# signal_processor_design_of_UAV.net
KiCad netlist of a schematic drawn in Altium Designer
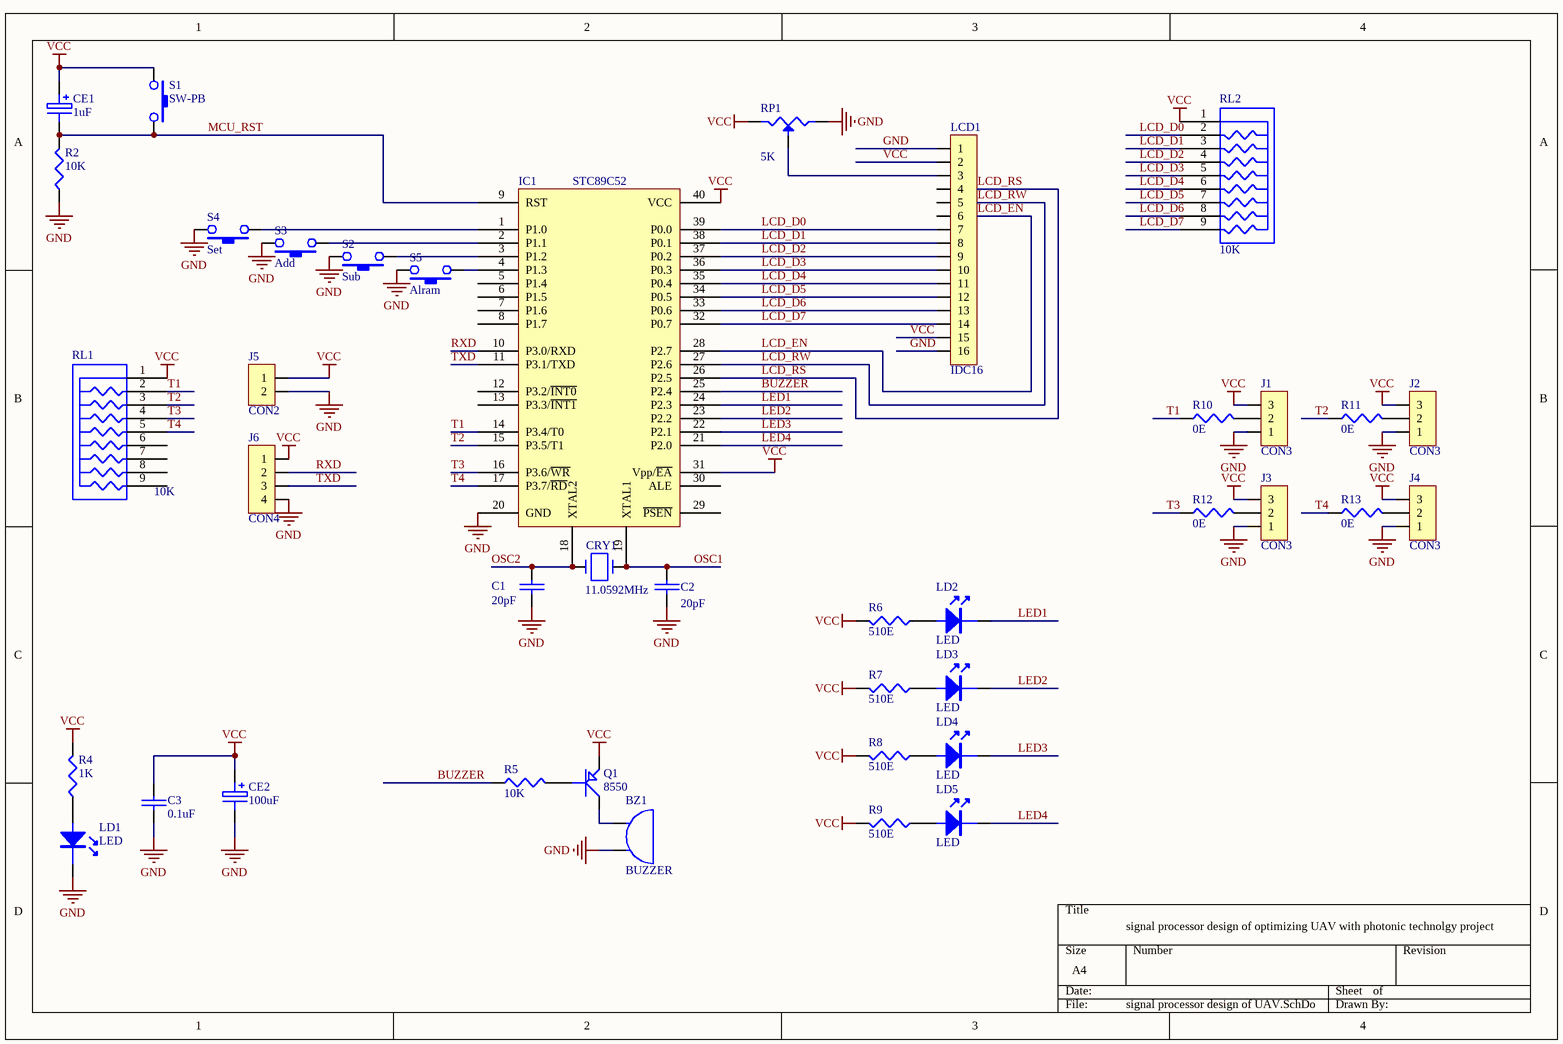
[diagram p0: signal processor design of UAV.SchDoc]

(export (version "E")
  (design (tool "Eeschema 10.0.6"))
  (components
    (comp (ref "BZ1") (value "BUZZER") (footprint "BUZZER1") (libsource (lib "Sch1") (part "BUZZER")))
    (comp (ref "C1")
      (value "20pF")
      (footprint "RAD0.1")
      (description "Capacitor")
      (libsource (lib "*") (part "CAP"))
    )
    (comp (ref "C2")
      (value "20pF")
      (footprint "RAD0.1")
      (description "Capacitor")
      (libsource (lib "*") (part "CAP"))
    )
    (comp (ref "C3") (value "0.1uF") (footprint "RAD0.1") (libsource (lib "Sch1") (part "CAP")))
    (comp (ref "CE1") (value "1uF") (footprint "RB.1/.1L") (libsource (lib "Sch1") (part "ELECTRO1")))
    (comp (ref "CE2") (value "100uF") (footprint "RB.1/.2") (libsource (lib "Sch1") (part "ELECTRO1")))
    (comp (ref "CRY1") (value "11.0592MHz") (footprint "XTAL1") (libsource (lib "*") (part "CRYSTAL")))
    (comp (ref "IC1") (value "STC89C52") (footprint "DIP40") (libsource (lib "Sch") (part "AT89C51")))
    (comp (ref "J1") (value "CON3") (footprint "HJ3P2.54") (libsource (lib "Sch1") (part "CON3")))
    (comp (ref "J2") (value "CON3") (footprint "HJ3P2.54") (libsource (lib "Sch1") (part "CON3")))
    (comp (ref "J3") (value "CON3") (footprint "HJ3P2.54") (libsource (lib "Sch1") (part "CON3")))
    (comp (ref "J4") (value "CON3") (footprint "HJ3P2.54") (libsource (lib "Sch1") (part "CON3")))
    (comp (ref "J5") (value "CON2") (footprint "HJ2P2.54") (libsource (lib "Sch1") (part "CON2")))
    (comp (ref "J6") (value "CON4") (footprint "HJ4P2.54") (libsource (lib "Sch1") (part "CON4")))
    (comp (ref "LCD1") (value "IDC16") (footprint "LCD1602A") (libsource (lib "Sch1") (part "CON16")))
    (comp (ref "LD1") (value "LED") (footprint "LEDF3") (libsource (lib "Sch1") (part "LED")))
    (comp (ref "LD2") (value "LED") (footprint "LEDF3") (libsource (lib "Sch1") (part "LED")))
    (comp (ref "LD3") (value "LED") (footprint "LEDF3") (libsource (lib "Sch1") (part "LED")))
    (comp (ref "LD4") (value "LED") (footprint "LEDF3") (libsource (lib "Sch1") (part "LED")))
    (comp (ref "LD5") (value "LED") (footprint "LEDF3") (libsource (lib "Sch1") (part "LED")))
    (comp (ref "Q1") (value "8550") (footprint "TR-EBC") (libsource (lib "Sch1") (part "PNP1")))
    (comp (ref "R2") (value "10K") (footprint "AXIAL0.3") (libsource (lib "Sch1") (part "RES1")))
    (comp (ref "R4") (value "1K") (footprint "AXIAL0.3") (libsource (lib "Sch1") (part "RES1")))
    (comp (ref "R5") (value "10K") (footprint "AXIAL0.3") (libsource (lib "Sch1") (part "RES1")))
    (comp (ref "R6") (value "510E") (footprint "AXIAL0.3") (libsource (lib "Sch1") (part "RES1")))
    (comp (ref "R7") (value "510E") (footprint "AXIAL0.3") (libsource (lib "Sch1") (part "RES1")))
    (comp (ref "R8") (value "510E") (footprint "AXIAL0.3") (libsource (lib "Sch1") (part "RES1")))
    (comp (ref "R9") (value "510E") (footprint "AXIAL0.3") (libsource (lib "Sch1") (part "RES1")))
    (comp (ref "R10") (value "0E") (footprint "AXIAL0.3") (libsource (lib "Sch1") (part "RES1")))
    (comp (ref "R11") (value "0E") (footprint "AXIAL0.3") (libsource (lib "Sch1") (part "RES1")))
    (comp (ref "R12") (value "0E") (footprint "AXIAL0.3") (libsource (lib "Sch1") (part "RES1")))
    (comp (ref "R13") (value "0E") (footprint "AXIAL0.3") (libsource (lib "Sch1") (part "RES1")))
    (comp (ref "RL1") (value "10K") (footprint "RES9P") (libsource (lib "Sch1") (part "RESL1")))
    (comp (ref "RL2") (value "10K") (footprint "RES9P") (libsource (lib "Sch1") (part "RESL1")))
    (comp (ref "RP1") (value "5K") (footprint "WR1") (libsource (lib "Sch1") (part "POT1")))
    (comp (ref "S1") (value "SW-PB") (footprint "SW-PB4DS") (libsource (lib "Sch1") (part "SW-PB")))
    (comp (ref "S2") (value "Sub") (footprint "SW-PB4DS") (libsource (lib "Sch1") (part "SW-PB")))
    (comp (ref "S3") (value "Add") (footprint "SW-PB4DS") (libsource (lib "Sch1") (part "SW-PB")))
    (comp (ref "S4") (value "Set") (footprint "SW-PB4DS") (libsource (lib "Sch1") (part "SW-PB")))
    (comp (ref "S5") (value "Alram") (footprint "SW-PB4DS") (libsource (lib "Sch1") (part "SW-PB")))
  )
  (nets
    (net (code "1") (name "/BUZZER") (class "Default")
      (node (ref "IC1") (pin "25") (pinfunction "P2.4_25") (pintype "passive"))
      (node (ref "R5") (pin "1") (pintype "passive"))
    )
    (net (code "2") (name "/LCD_D0") (class "Default")
      (node (ref "IC1") (pin "39") (pinfunction "P0.0_39") (pintype "passive"))
      (node (ref "LCD1") (pin "7") (pinfunction "7_7") (pintype "passive"))
      (node (ref "RL2") (pin "2") (pinfunction "2_2") (pintype "passive"))
    )
    (net (code "3") (name "/LCD_D1") (class "Default")
      (node (ref "IC1") (pin "38") (pinfunction "P0.1_38") (pintype "passive"))
      (node (ref "LCD1") (pin "8") (pinfunction "8_8") (pintype "passive"))
      (node (ref "RL2") (pin "3") (pinfunction "3_3") (pintype "passive"))
    )
    (net (code "4") (name "/LCD_D2") (class "Default")
      (node (ref "IC1") (pin "37") (pinfunction "P0.2_37") (pintype "passive"))
      (node (ref "LCD1") (pin "9") (pinfunction "9_9") (pintype "passive"))
      (node (ref "RL2") (pin "4") (pinfunction "4_4") (pintype "passive"))
    )
    (net (code "5") (name "/LCD_D3") (class "Default")
      (node (ref "IC1") (pin "36") (pinfunction "P0.3_36") (pintype "passive"))
      (node (ref "LCD1") (pin "10") (pinfunction "10_10") (pintype "passive"))
      (node (ref "RL2") (pin "5") (pinfunction "5_5") (pintype "passive"))
    )
    (net (code "6") (name "/LCD_D4") (class "Default")
      (node (ref "IC1") (pin "35") (pinfunction "P0.4_35") (pintype "passive"))
      (node (ref "LCD1") (pin "11") (pinfunction "11_11") (pintype "passive"))
      (node (ref "RL2") (pin "6") (pinfunction "6_6") (pintype "passive"))
    )
    (net (code "7") (name "/LCD_D5") (class "Default")
      (node (ref "IC1") (pin "34") (pinfunction "P0.5_34") (pintype "passive"))
      (node (ref "LCD1") (pin "12") (pinfunction "12_12") (pintype "passive"))
      (node (ref "RL2") (pin "7") (pinfunction "7_7") (pintype "passive"))
    )
    (net (code "8") (name "/LCD_D6") (class "Default")
      (node (ref "IC1") (pin "33") (pinfunction "P0.6_33") (pintype "passive"))
      (node (ref "LCD1") (pin "13") (pinfunction "13_13") (pintype "passive"))
      (node (ref "RL2") (pin "8") (pinfunction "8_8") (pintype "passive"))
    )
    (net (code "9") (name "/LCD_D7") (class "Default")
      (node (ref "IC1") (pin "32") (pinfunction "P0.7_32") (pintype "passive"))
      (node (ref "LCD1") (pin "14") (pinfunction "14_14") (pintype "passive"))
      (node (ref "RL2") (pin "9") (pinfunction "9_9") (pintype "passive"))
    )
    (net (code "10") (name "/LCD_EN") (class "Default")
      (node (ref "IC1") (pin "28") (pinfunction "P2.7_28") (pintype "passive"))
    )
    (net (code "11") (name "/LCD_RS") (class "Default")
      (node (ref "IC1") (pin "26") (pinfunction "P2.5_26") (pintype "passive"))
    )
    (net (code "12") (name "/LCD_RW") (class "Default")
      (node (ref "IC1") (pin "27") (pinfunction "P2.6_27") (pintype "passive"))
    )
    (net (code "13") (name "/LED1") (class "Default")
      (node (ref "IC1") (pin "24") (pinfunction "P2.3_24") (pintype "passive"))
      (node (ref "LD2") (pin "K") (pintype "passive"))
    )
    (net (code "14") (name "/LED2") (class "Default")
      (node (ref "IC1") (pin "23") (pinfunction "P2.2_23") (pintype "passive"))
      (node (ref "LD3") (pin "K") (pintype "passive"))
    )
    (net (code "15") (name "/LED3") (class "Default")
      (node (ref "IC1") (pin "22") (pinfunction "P2.1_22") (pintype "passive"))
      (node (ref "LD4") (pin "K") (pintype "passive"))
    )
    (net (code "16") (name "/LED4") (class "Default")
      (node (ref "IC1") (pin "21") (pinfunction "P2.0_21") (pintype "passive"))
      (node (ref "LD5") (pin "K") (pintype "passive"))
    )
    (net (code "17") (name "/MCU_RST") (class "Default")
      (node (ref "CE1") (pin "2") (pintype "passive"))
      (node (ref "IC1") (pin "9") (pinfunction "RST_9") (pintype "passive"))
      (node (ref "R2") (pin "2") (pintype "passive"))
      (node (ref "S1") (pin "2") (pintype "passive"))
    )
    (net (code "18") (name "/OSC1") (class "Default")
      (node (ref "C2") (pin "1") (pinfunction "1_1") (pintype "passive"))
      (node (ref "CRY1") (pin "2") (pinfunction "2_2") (pintype "passive"))
      (node (ref "IC1") (pin "19") (pinfunction "XTAL1_19") (pintype "passive"))
    )
    (net (code "19") (name "/OSC2") (class "Default")
      (node (ref "C1") (pin "1") (pinfunction "1_1") (pintype "passive"))
      (node (ref "CRY1") (pin "1") (pinfunction "1_1") (pintype "passive"))
      (node (ref "IC1") (pin "18") (pinfunction "XTAL2_18") (pintype "passive"))
    )
    (net (code "20") (name "/RXD") (class "Default")
      (node (ref "IC1") (pin "10") (pinfunction "P3.0/RXD_10") (pintype "passive"))
      (node (ref "J6") (pin "2") (pinfunction "2_2") (pintype "passive"))
    )
    (net (code "21") (name "/T1") (class "Default")
      (node (ref "IC1") (pin "14") (pinfunction "P3.4/T0_14") (pintype "passive"))
      (node (ref "R10") (pin "1") (pintype "passive"))
      (node (ref "RL1") (pin "2") (pinfunction "2_2") (pintype "passive"))
    )
    (net (code "22") (name "/T2") (class "Default")
      (node (ref "IC1") (pin "15") (pinfunction "P3.5/T1_15") (pintype "passive"))
      (node (ref "R11") (pin "1") (pintype "passive"))
      (node (ref "RL1") (pin "3") (pinfunction "3_3") (pintype "passive"))
    )
    (net (code "23") (name "/T3") (class "Default")
      (node (ref "IC1") (pin "16") (pinfunction "P3.6/~{WR}_16") (pintype "passive"))
      (node (ref "R12") (pin "1") (pintype "passive"))
      (node (ref "RL1") (pin "4") (pinfunction "4_4") (pintype "passive"))
    )
    (net (code "24") (name "/T4") (class "Default")
      (node (ref "IC1") (pin "17") (pinfunction "P3.7/~{RD}_17") (pintype "passive"))
      (node (ref "R13") (pin "1") (pintype "passive"))
      (node (ref "RL1") (pin "5") (pinfunction "5_5") (pintype "passive"))
    )
    (net (code "25") (name "/TXD") (class "Default")
      (node (ref "IC1") (pin "11") (pinfunction "P3.1/TXD_11") (pintype "passive"))
      (node (ref "J6") (pin "3") (pinfunction "3_3") (pintype "passive"))
    )
    (net (code "26") (name "GND") (class "Default")
      (node (ref "BZ1") (pin "2") (pintype "passive"))
      (node (ref "C1") (pin "2") (pinfunction "2_2") (pintype "passive"))
      (node (ref "C2") (pin "2") (pinfunction "2_2") (pintype "passive"))
      (node (ref "C3") (pin "2") (pintype "passive"))
      (node (ref "CE2") (pin "2") (pintype "passive"))
      (node (ref "IC1") (pin "20") (pinfunction "GND_20") (pintype "passive"))
      (node (ref "J1") (pin "1") (pinfunction "1_1") (pintype "passive"))
      (node (ref "J2") (pin "1") (pinfunction "1_1") (pintype "passive"))
      (node (ref "J3") (pin "1") (pinfunction "1_1") (pintype "passive"))
      (node (ref "J4") (pin "1") (pinfunction "1_1") (pintype "passive"))
      (node (ref "J5") (pin "2") (pinfunction "2_2") (pintype "passive"))
      (node (ref "J6") (pin "4") (pinfunction "4_4") (pintype "passive"))
      (node (ref "LCD1") (pin "1") (pinfunction "1_1") (pintype "passive"))
      (node (ref "LCD1") (pin "16") (pinfunction "16_16") (pintype "passive"))
      (node (ref "LD1") (pin "K") (pintype "passive"))
      (node (ref "R2") (pin "1") (pintype "passive"))
      (node (ref "RP1") (pin "2") (pintype "passive"))
      (node (ref "S2") (pin "1") (pintype "passive"))
      (node (ref "S3") (pin "1") (pintype "passive"))
      (node (ref "S4") (pin "1") (pintype "passive"))
      (node (ref "S5") (pin "1") (pintype "passive"))
    )
    (net (code "27") (name "Net-(BZ1-Pad1)") (class "Default")
      (node (ref "BZ1") (pin "1") (pintype "passive"))
      (node (ref "Q1") (pin "COLL") (pinfunction "COLL_COLL") (pintype "passive"))
    )
    (net (code "28") (name "Net-(IC1-P1.0)") (class "Default")
      (node (ref "IC1") (pin "1") (pinfunction "P1.0_1") (pintype "passive"))
      (node (ref "S4") (pin "2") (pintype "passive"))
    )
    (net (code "29") (name "Net-(IC1-P1.1)") (class "Default")
      (node (ref "IC1") (pin "2") (pinfunction "P1.1_2") (pintype "passive"))
      (node (ref "S3") (pin "2") (pintype "passive"))
    )
    (net (code "30") (name "Net-(IC1-P1.2)") (class "Default")
      (node (ref "IC1") (pin "3") (pinfunction "P1.2_3") (pintype "passive"))
      (node (ref "S2") (pin "2") (pintype "passive"))
    )
    (net (code "31") (name "Net-(IC1-P1.3)") (class "Default")
      (node (ref "IC1") (pin "4") (pinfunction "P1.3_4") (pintype "passive"))
      (node (ref "S5") (pin "2") (pintype "passive"))
    )
    (net (code "32") (name "Net-(J1-Pad2)") (class "Default")
      (node (ref "J1") (pin "2") (pinfunction "2_2") (pintype "passive"))
      (node (ref "R10") (pin "2") (pintype "passive"))
    )
    (net (code "33") (name "Net-(J2-Pad2)") (class "Default")
      (node (ref "J2") (pin "2") (pinfunction "2_2") (pintype "passive"))
      (node (ref "R11") (pin "2") (pintype "passive"))
    )
    (net (code "34") (name "Net-(J3-Pad2)") (class "Default")
      (node (ref "J3") (pin "2") (pinfunction "2_2") (pintype "passive"))
      (node (ref "R12") (pin "2") (pintype "passive"))
    )
    (net (code "35") (name "Net-(J4-Pad2)") (class "Default")
      (node (ref "J4") (pin "2") (pinfunction "2_2") (pintype "passive"))
      (node (ref "R13") (pin "2") (pintype "passive"))
    )
    (net (code "36") (name "Net-(LCD1-Pad3)") (class "Default")
      (node (ref "LCD1") (pin "3") (pinfunction "3_3") (pintype "passive"))
      (node (ref "RP1") (pin "W") (pintype "passive"))
    )
    (net (code "37") (name "Net-(LD1-PadA)") (class "Default")
      (node (ref "LD1") (pin "A") (pintype "passive"))
      (node (ref "R4") (pin "1") (pintype "passive"))
    )
    (net (code "38") (name "Net-(LD2-PadA)") (class "Default")
      (node (ref "LD2") (pin "A") (pintype "passive"))
      (node (ref "R6") (pin "1") (pintype "passive"))
    )
    (net (code "39") (name "Net-(LD3-PadA)") (class "Default")
      (node (ref "LD3") (pin "A") (pintype "passive"))
      (node (ref "R7") (pin "1") (pintype "passive"))
    )
    (net (code "40") (name "Net-(LD4-PadA)") (class "Default")
      (node (ref "LD4") (pin "A") (pintype "passive"))
      (node (ref "R8") (pin "1") (pintype "passive"))
    )
    (net (code "41") (name "Net-(LD5-PadA)") (class "Default")
      (node (ref "LD5") (pin "A") (pintype "passive"))
      (node (ref "R9") (pin "1") (pintype "passive"))
    )
    (net (code "42") (name "Net-(Q1-PadBASE)") (class "Default")
      (node (ref "Q1") (pin "BASE") (pinfunction "BASE_BASE") (pintype "passive"))
      (node (ref "R5") (pin "2") (pintype "passive"))
    )
    (net (code "43") (name "VCC") (class "Default")
      (node (ref "C3") (pin "1") (pintype "passive"))
      (node (ref "CE1") (pin "1") (pintype "passive"))
      (node (ref "CE2") (pin "1") (pintype "passive"))
      (node (ref "IC1") (pin "31") (pinfunction "Vpp/~{EA}_31") (pintype "passive"))
      (node (ref "IC1") (pin "40") (pinfunction "VCC_40") (pintype "passive"))
      (node (ref "J1") (pin "3") (pinfunction "3_3") (pintype "passive"))
      (node (ref "J2") (pin "3") (pinfunction "3_3") (pintype "passive"))
      (node (ref "J3") (pin "3") (pinfunction "3_3") (pintype "passive"))
      (node (ref "J4") (pin "3") (pinfunction "3_3") (pintype "passive"))
      (node (ref "J5") (pin "1") (pinfunction "1_1") (pintype "passive"))
      (node (ref "J6") (pin "1") (pinfunction "1_1") (pintype "passive"))
      (node (ref "LCD1") (pin "15") (pinfunction "15_15") (pintype "passive"))
      (node (ref "LCD1") (pin "2") (pinfunction "2_2") (pintype "passive"))
      (node (ref "Q1") (pin "EMIT") (pinfunction "EMIT_EMIT") (pintype "passive"))
      (node (ref "R4") (pin "2") (pintype "passive"))
      (node (ref "R6") (pin "2") (pintype "passive"))
      (node (ref "R7") (pin "2") (pintype "passive"))
      (node (ref "R8") (pin "2") (pintype "passive"))
      (node (ref "R9") (pin "2") (pintype "passive"))
      (node (ref "RL1") (pin "1") (pinfunction "1_1") (pintype "passive"))
      (node (ref "RL2") (pin "1") (pinfunction "1_1") (pintype "passive"))
      (node (ref "RP1") (pin "1") (pintype "passive"))
      (node (ref "S1") (pin "1") (pintype "passive"))
    )
    (net (code "44") (name "unconnected-(IC1-ALE-Pad30)") (class "Default")
      (node (ref "IC1") (pin "30") (pinfunction "ALE_30") (pintype "passive"))
    )
    (net (code "45") (name "unconnected-(IC1-P1.4-Pad5)") (class "Default")
      (node (ref "IC1") (pin "5") (pinfunction "P1.4_5") (pintype "passive"))
    )
    (net (code "46") (name "unconnected-(IC1-P1.5-Pad6)") (class "Default")
      (node (ref "IC1") (pin "6") (pinfunction "P1.5_6") (pintype "passive"))
    )
    (net (code "47") (name "unconnected-(IC1-P1.6-Pad7)") (class "Default")
      (node (ref "IC1") (pin "7") (pinfunction "P1.6_7") (pintype "passive"))
    )
    (net (code "48") (name "unconnected-(IC1-P1.7-Pad8)") (class "Default")
      (node (ref "IC1") (pin "8") (pinfunction "P1.7_8") (pintype "passive"))
    )
    (net (code "49") (name "unconnected-(IC1-P3.2{slash}~{INT0}-Pad12)") (class "Default")
      (node (ref "IC1") (pin "12") (pinfunction "P3.2/~{INT0}_12") (pintype "passive"))
    )
    (net (code "50") (name "unconnected-(IC1-P3.3{slash}~{INT1}-Pad13)") (class "Default")
      (node (ref "IC1") (pin "13") (pinfunction "P3.3/~{INT1}_13") (pintype "passive"))
    )
    (net (code "51") (name "unconnected-(IC1-~{PSEN}-Pad29)") (class "Default")
      (node (ref "IC1") (pin "29") (pinfunction "~{PSEN}_29") (pintype "passive"))
    )
    (net (code "52") (name "unconnected-(LCD1-Pad4)") (class "Default")
      (node (ref "LCD1") (pin "4") (pinfunction "4_4") (pintype "passive"))
    )
    (net (code "53") (name "unconnected-(LCD1-Pad5)") (class "Default")
      (node (ref "LCD1") (pin "5") (pinfunction "5_5") (pintype "passive"))
    )
    (net (code "54") (name "unconnected-(LCD1-Pad6)") (class "Default")
      (node (ref "LCD1") (pin "6") (pinfunction "6_6") (pintype "passive"))
    )
    (net (code "55") (name "unconnected-(RL1-Pad6)") (class "Default")
      (node (ref "RL1") (pin "6") (pinfunction "6_6") (pintype "passive"))
    )
    (net (code "56") (name "unconnected-(RL1-Pad7)") (class "Default")
      (node (ref "RL1") (pin "7") (pinfunction "7_7") (pintype "passive"))
    )
    (net (code "57") (name "unconnected-(RL1-Pad8)") (class "Default")
      (node (ref "RL1") (pin "8") (pinfunction "8_8") (pintype "passive"))
    )
    (net (code "58") (name "unconnected-(RL1-Pad9)") (class "Default")
      (node (ref "RL1") (pin "9") (pinfunction "9_9") (pintype "passive"))
    )
  )
)
